# untitled.net
KiCad netlist of a schematic drawn in EAGLE
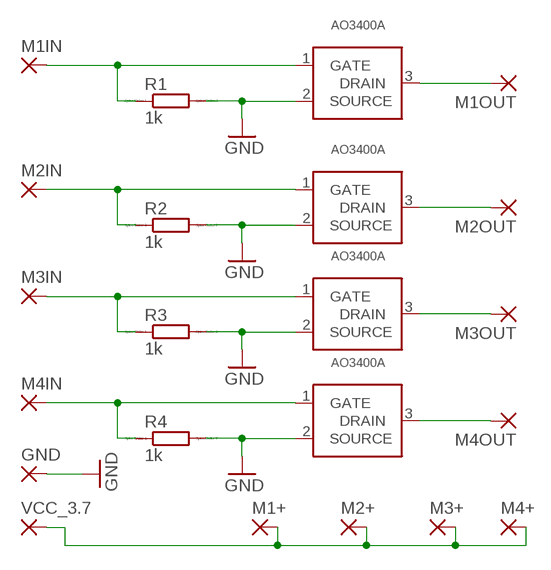
[diagram p0: schematic, sheet 1]

(export (version "E")
  (design (tool "Eeschema 10.0.6"))
  (components
    (comp (ref "GND")
      (value "SMD2")
      (footprint "eagle-import:SMD1,27-2,54")
      (libsource (lib "eagle-import") (part "SMD2"))
    )
    (comp (ref "M1+")
      (value "SMD2")
      (footprint "eagle-import:SMD1,27-2,54")
      (libsource (lib "eagle-import") (part "SMD2"))
    )
    (comp (ref "M1IN")
      (value "SMD2")
      (footprint "eagle-import:SMD1,27-2,54")
      (libsource (lib "eagle-import") (part "SMD2"))
    )
    (comp (ref "M1OUT")
      (value "SMD2")
      (footprint "eagle-import:SMD1,27-2,54")
      (libsource (lib "eagle-import") (part "SMD2"))
    )
    (comp (ref "M2+")
      (value "SMD2")
      (footprint "eagle-import:SMD1,27-2,54")
      (libsource (lib "eagle-import") (part "SMD2"))
    )
    (comp (ref "M2IN")
      (value "SMD2")
      (footprint "eagle-import:SMD1,27-2,54")
      (libsource (lib "eagle-import") (part "SMD2"))
    )
    (comp (ref "M2OUT")
      (value "SMD2")
      (footprint "eagle-import:SMD1,27-2,54")
      (libsource (lib "eagle-import") (part "SMD2"))
    )
    (comp (ref "M3+")
      (value "SMD2")
      (footprint "eagle-import:SMD1,27-2,54")
      (libsource (lib "eagle-import") (part "SMD2"))
    )
    (comp (ref "M3IN")
      (value "SMD2")
      (footprint "eagle-import:SMD1,27-2,54")
      (libsource (lib "eagle-import") (part "SMD2"))
    )
    (comp (ref "M3OUT")
      (value "SMD2")
      (footprint "eagle-import:SMD1,27-2,54")
      (libsource (lib "eagle-import") (part "SMD2"))
    )
    (comp (ref "M4+")
      (value "SMD2")
      (footprint "eagle-import:SMD1,27-2,54")
      (libsource (lib "eagle-import") (part "SMD2"))
    )
    (comp (ref "M4IN")
      (value "SMD2")
      (footprint "eagle-import:SMD1,27-2,54")
      (libsource (lib "eagle-import") (part "SMD2"))
    )
    (comp (ref "M4OUT")
      (value "SMD2")
      (footprint "eagle-import:SMD1,27-2,54")
      (libsource (lib "eagle-import") (part "SMD2"))
    )
    (comp (ref "R1")
      (value "1k")
      (footprint "eagle-import:R1206")
      (libsource (lib "eagle-import") (part "RR1206"))
    )
    (comp (ref "R2")
      (value "1k")
      (footprint "eagle-import:R1206")
      (libsource (lib "eagle-import") (part "RR1206"))
    )
    (comp (ref "R3")
      (value "1k")
      (footprint "eagle-import:R1206")
      (libsource (lib "eagle-import") (part "RR1206"))
    )
    (comp (ref "R4")
      (value "1k")
      (footprint "eagle-import:R1206")
      (libsource (lib "eagle-import") (part "RR1206"))
    )
    (comp (ref "U$1")
      (value "AO3400A")
      (footprint "eagle-import:SOT-23")
      (libsource (lib "eagle-import") (part "AO3400A"))
    )
    (comp (ref "U$2")
      (value "AO3400A")
      (footprint "eagle-import:SOT-23")
      (libsource (lib "eagle-import") (part "AO3400A"))
    )
    (comp (ref "U$3")
      (value "AO3400A")
      (footprint "eagle-import:SOT-23")
      (libsource (lib "eagle-import") (part "AO3400A"))
    )
    (comp (ref "U$4")
      (value "AO3400A")
      (footprint "eagle-import:SOT-23")
      (libsource (lib "eagle-import") (part "AO3400A"))
    )
    (comp (ref "VCC_3.7")
      (value "SMD2")
      (footprint "eagle-import:SMD1,27-2,54")
      (libsource (lib "eagle-import") (part "SMD2"))
    )
  )
  (nets
    (net (code "1") (name "GND") (class "Default")
      (node (ref "GND") (pin "1") (pinfunction "P_1") (pintype "passive"))
      (node (ref "R1") (pin "2") (pinfunction "2_2") (pintype "passive"))
      (node (ref "R2") (pin "2") (pinfunction "2_2") (pintype "passive"))
      (node (ref "R3") (pin "2") (pinfunction "2_2") (pintype "passive"))
      (node (ref "R4") (pin "2") (pinfunction "2_2") (pintype "passive"))
      (node (ref "U$1") (pin "2") (pinfunction "SOURCE_2") (pintype "bidirectional"))
      (node (ref "U$2") (pin "2") (pinfunction "SOURCE_2") (pintype "bidirectional"))
      (node (ref "U$3") (pin "2") (pinfunction "SOURCE_2") (pintype "bidirectional"))
      (node (ref "U$4") (pin "2") (pinfunction "SOURCE_2") (pintype "bidirectional"))
    )
    (net (code "2") (name "Net-(M1+-P)") (class "Default")
      (node (ref "M1+") (pin "1") (pinfunction "P_1") (pintype "passive"))
      (node (ref "M2+") (pin "1") (pinfunction "P_1") (pintype "passive"))
      (node (ref "M3+") (pin "1") (pinfunction "P_1") (pintype "passive"))
      (node (ref "M4+") (pin "1") (pinfunction "P_1") (pintype "passive"))
      (node (ref "VCC_3.7") (pin "1") (pinfunction "P_1") (pintype "passive"))
    )
    (net (code "3") (name "Net-(M1IN-P)") (class "Default")
      (node (ref "M1IN") (pin "1") (pinfunction "P_1") (pintype "passive"))
      (node (ref "R1") (pin "1") (pinfunction "1_1") (pintype "passive"))
      (node (ref "U$1") (pin "1") (pinfunction "GATE_1") (pintype "bidirectional"))
    )
    (net (code "4") (name "Net-(M1OUT-P)") (class "Default")
      (node (ref "M1OUT") (pin "1") (pinfunction "P_1") (pintype "passive"))
      (node (ref "U$1") (pin "3") (pinfunction "DRAIN_3") (pintype "bidirectional"))
    )
    (net (code "5") (name "Net-(M2IN-P)") (class "Default")
      (node (ref "M2IN") (pin "1") (pinfunction "P_1") (pintype "passive"))
      (node (ref "R2") (pin "1") (pinfunction "1_1") (pintype "passive"))
      (node (ref "U$2") (pin "1") (pinfunction "GATE_1") (pintype "bidirectional"))
    )
    (net (code "6") (name "Net-(M2OUT-P)") (class "Default")
      (node (ref "M2OUT") (pin "1") (pinfunction "P_1") (pintype "passive"))
      (node (ref "U$2") (pin "3") (pinfunction "DRAIN_3") (pintype "bidirectional"))
    )
    (net (code "7") (name "Net-(M3IN-P)") (class "Default")
      (node (ref "M3IN") (pin "1") (pinfunction "P_1") (pintype "passive"))
      (node (ref "R3") (pin "1") (pinfunction "1_1") (pintype "passive"))
      (node (ref "U$3") (pin "1") (pinfunction "GATE_1") (pintype "bidirectional"))
    )
    (net (code "8") (name "Net-(M3OUT-P)") (class "Default")
      (node (ref "M3OUT") (pin "1") (pinfunction "P_1") (pintype "passive"))
      (node (ref "U$3") (pin "3") (pinfunction "DRAIN_3") (pintype "bidirectional"))
    )
    (net (code "9") (name "Net-(M4IN-P)") (class "Default")
      (node (ref "M4IN") (pin "1") (pinfunction "P_1") (pintype "passive"))
      (node (ref "R4") (pin "1") (pinfunction "1_1") (pintype "passive"))
      (node (ref "U$4") (pin "1") (pinfunction "GATE_1") (pintype "bidirectional"))
    )
    (net (code "10") (name "Net-(M4OUT-P)") (class "Default")
      (node (ref "M4OUT") (pin "1") (pinfunction "P_1") (pintype "passive"))
      (node (ref "U$4") (pin "3") (pinfunction "DRAIN_3") (pintype "bidirectional"))
    )
  )
)
